# MainProc.net
KiCad netlist of a schematic drawn in Altium Designer
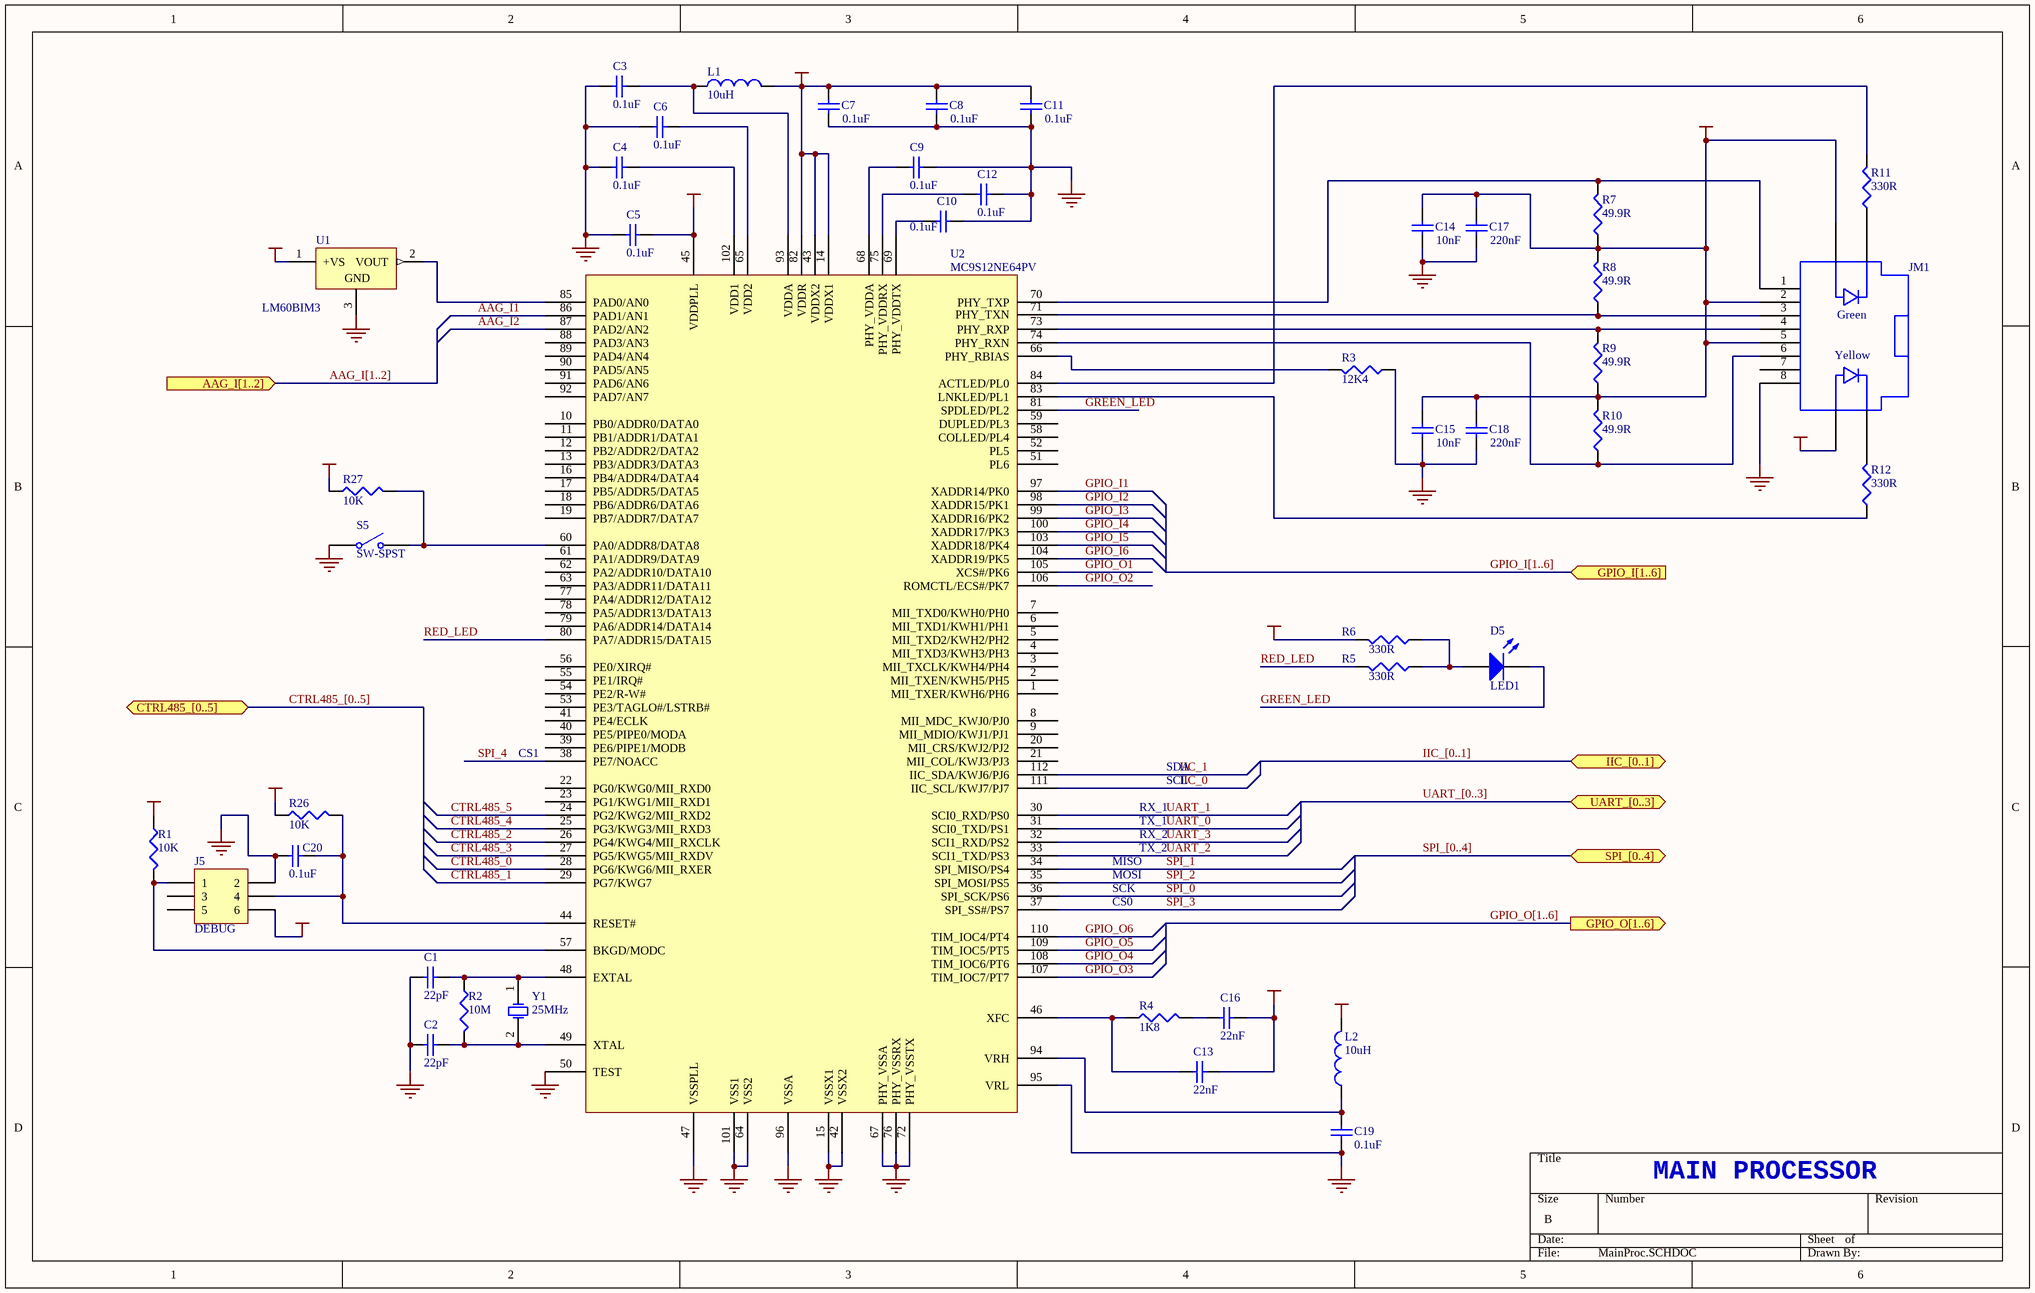
[diagram p0: MainProc.SCHDOC]

(export (version "E")
  (design (tool "Eeschema 10.0.6"))
  (components
    (comp (ref "C1")
      (value "22pF")
      (footprint "_1206")
      (description "Capacitor (Semiconductor SIM Model)")
      (fields (field (name "Comment") "Cap Semi") (field (name "PUBLISHER") "Altium Limited"))
      (libsource (lib "Miscellaneous Devices") (part "Cap Semi"))
    )
    (comp (ref "C2")
      (value "22pF")
      (footprint "_1206")
      (description "Capacitor (Semiconductor SIM Model)")
      (fields (field (name "Comment") "Cap Semi") (field (name "PUBLISHER") "Altium Limited"))
      (libsource (lib "Miscellaneous Devices") (part "Cap Semi"))
    )
    (comp (ref "C3")
      (value "0.1uF")
      (footprint "_0805")
      (description "Capacitor (Semiconductor SIM Model)")
      (fields (field (name "Comment") "Cap Semi") (field (name "PUBLISHER") "Altium Limited"))
      (libsource (lib "Miscellaneous Devices") (part "Cap Semi"))
    )
    (comp (ref "C4")
      (value "0.1uF")
      (footprint "_0805")
      (description "Capacitor (Semiconductor SIM Model)")
      (fields (field (name "Comment") "Cap Semi") (field (name "PUBLISHER") "Altium Limited"))
      (libsource (lib "Miscellaneous Devices") (part "Cap Semi"))
    )
    (comp (ref "C5")
      (value "0.1uF")
      (footprint "_0805")
      (description "Capacitor (Semiconductor SIM Model)")
      (fields (field (name "Comment") "Cap Semi") (field (name "PUBLISHER") "Altium Limited"))
      (libsource (lib "Miscellaneous Devices") (part "Cap Semi"))
    )
    (comp (ref "C6")
      (value "0.1uF")
      (footprint "_0805")
      (description "Capacitor (Semiconductor SIM Model)")
      (fields (field (name "Comment") "Cap Semi") (field (name "PUBLISHER") "Altium Limited"))
      (libsource (lib "Miscellaneous Devices") (part "Cap Semi"))
    )
    (comp (ref "C7")
      (value "0.1uF")
      (footprint "_0805")
      (description "Capacitor (Semiconductor SIM Model)")
      (fields (field (name "Comment") "Cap Semi") (field (name "PUBLISHER") "Altium Limited"))
      (libsource (lib "Miscellaneous Devices") (part "Cap Semi"))
    )
    (comp (ref "C8")
      (value "0.1uF")
      (footprint "_0805")
      (description "Capacitor (Semiconductor SIM Model)")
      (fields (field (name "Comment") "Cap Semi") (field (name "PUBLISHER") "Altium Limited"))
      (libsource (lib "Miscellaneous Devices") (part "Cap Semi"))
    )
    (comp (ref "C9")
      (value "0.1uF")
      (footprint "_0805")
      (description "Capacitor (Semiconductor SIM Model)")
      (fields (field (name "Comment") "Cap Semi") (field (name "PUBLISHER") "Altium Limited"))
      (libsource (lib "Miscellaneous Devices") (part "Cap Semi"))
    )
    (comp (ref "C10")
      (value "0.1uF")
      (footprint "_0805")
      (description "Capacitor (Semiconductor SIM Model)")
      (fields (field (name "Comment") "Cap Semi") (field (name "PUBLISHER") "Altium Limited"))
      (libsource (lib "Miscellaneous Devices") (part "Cap Semi"))
    )
    (comp (ref "C11")
      (value "0.1uF")
      (footprint "_0805")
      (description "Capacitor (Semiconductor SIM Model)")
      (fields (field (name "Comment") "Cap Semi") (field (name "PUBLISHER") "Altium Limited"))
      (libsource (lib "Miscellaneous Devices") (part "Cap Semi"))
    )
    (comp (ref "C12")
      (value "0.1uF")
      (footprint "_0805")
      (description "Capacitor (Semiconductor SIM Model)")
      (fields (field (name "Comment") "Cap Semi") (field (name "PUBLISHER") "Altium Limited"))
      (libsource (lib "Miscellaneous Devices") (part "Cap Semi"))
    )
    (comp (ref "C13")
      (value "22nF")
      (footprint "_0805")
      (description "Capacitor (Semiconductor SIM Model)")
      (fields (field (name "Comment") "Cap Semi") (field (name "PUBLISHER") "Altium Limited"))
      (libsource (lib "Miscellaneous Devices") (part "Cap Semi"))
    )
    (comp (ref "C14")
      (value "10nF")
      (footprint "_0805")
      (description "Capacitor (Semiconductor SIM Model)")
      (fields (field (name "Comment") "Cap Semi") (field (name "PUBLISHER") "Altium Limited"))
      (libsource (lib "Miscellaneous Devices") (part "Cap Semi"))
    )
    (comp (ref "C15")
      (value "10nF")
      (footprint "_0805")
      (description "Capacitor (Semiconductor SIM Model)")
      (fields (field (name "Comment") "Cap Semi") (field (name "PUBLISHER") "Altium Limited"))
      (libsource (lib "Miscellaneous Devices") (part "Cap Semi"))
    )
    (comp (ref "C16")
      (value "22nF")
      (footprint "_0805")
      (description "Capacitor (Semiconductor SIM Model)")
      (fields (field (name "Comment") "Cap Semi") (field (name "PUBLISHER") "Altium Limited"))
      (libsource (lib "Miscellaneous Devices") (part "Cap Semi"))
    )
    (comp (ref "C17")
      (value "220nF")
      (footprint "_0805")
      (description "Capacitor (Semiconductor SIM Model)")
      (fields (field (name "Comment") "Cap Semi") (field (name "PUBLISHER") "Altium Limited"))
      (libsource (lib "Miscellaneous Devices") (part "Cap Semi"))
    )
    (comp (ref "C18")
      (value "220nF")
      (footprint "_0805")
      (description "Capacitor (Semiconductor SIM Model)")
      (fields (field (name "Comment") "Cap Semi") (field (name "PUBLISHER") "Altium Limited"))
      (libsource (lib "Miscellaneous Devices") (part "Cap Semi"))
    )
    (comp (ref "C19")
      (value "0.1uF")
      (footprint "_0805")
      (description "Capacitor (Semiconductor SIM Model)")
      (fields (field (name "Comment") "Cap Semi") (field (name "PUBLISHER") "Altium Limited"))
      (libsource (lib "Miscellaneous Devices") (part "Cap Semi"))
    )
    (comp (ref "C20")
      (value "0.1uF")
      (footprint "_0805")
      (description "Capacitor (Semiconductor SIM Model)")
      (fields (field (name "Comment") "Cap Semi") (field (name "PUBLISHER") "Altium Limited"))
      (libsource (lib "Miscellaneous Devices") (part "Cap Semi"))
    )
    (comp (ref "D5")
      (value "LED1")
      (footprint "LED_PCB")
      (description "Typical RED GaAs LED")
      (fields (field (name "PUBLISHER") "Altium Limited"))
      (libsource (lib "Miscellaneous Devices") (part "LED1"))
    )
    (comp (ref "J5")
      (value "DEBUG")
      (footprint "HDR2X3")
      (description "Header, 3-Pin, Dual row")
      (fields (field (name "PUBLISHER") "Altium Limited"))
      (libsource (lib "Miscellaneous Connectors") (part "Header 3X2"))
    )
    (comp (ref "JM1")
      (value "JACK_RJ45_LED")
      (footprint "JACK_RJ45_LEDS")
      (description "RJ45 Connector Jack with Leds")
      (libsource (lib "Custom") (part "JACK_RJ45_LED"))
    )
    (comp (ref "L1")
      (value "10uH")
      (footprint "_0805")
      (description "Inductor")
      (fields (field (name "PUBLISHER") "Altium Limited"))
      (libsource (lib "Miscellaneous Devices") (part "Inductor"))
    )
    (comp (ref "L2")
      (value "10uH")
      (footprint "_0805")
      (description "Inductor")
      (fields (field (name "PUBLISHER") "Altium Limited"))
      (libsource (lib "Miscellaneous Devices") (part "Inductor"))
    )
    (comp (ref "R1")
      (value "10K")
      (footprint "_0805")
      (description "Resistor")
      (fields (field (name "Comment") "Res3") (field (name "PUBLISHER") "Altium Limited"))
      (libsource (lib "Miscellaneous Devices") (part "Res3"))
    )
    (comp (ref "R2")
      (value "10M")
      (footprint "_1206")
      (description "Resistor")
      (fields (field (name "Comment") "Res3") (field (name "PUBLISHER") "Altium Limited"))
      (libsource (lib "Miscellaneous Devices") (part "Res3"))
    )
    (comp (ref "R3")
      (value "12K4")
      (footprint "_0805")
      (description "Resistor")
      (fields (field (name "Comment") "Res3") (field (name "PUBLISHER") "Altium Limited"))
      (libsource (lib "Miscellaneous Devices") (part "Res3"))
    )
    (comp (ref "R4")
      (value "1K8")
      (footprint "_0805")
      (description "Resistor")
      (fields (field (name "Comment") "Res3") (field (name "PUBLISHER") "Altium Limited"))
      (libsource (lib "Miscellaneous Devices") (part "Res3"))
    )
    (comp (ref "R5")
      (value "330R")
      (footprint "_0805")
      (description "Resistor")
      (fields (field (name "Comment") "Res3") (field (name "PUBLISHER") "Altium Limited"))
      (libsource (lib "Miscellaneous Devices") (part "Res3"))
    )
    (comp (ref "R6")
      (value "330R")
      (footprint "_0805")
      (description "Resistor")
      (fields (field (name "Comment") "Res3") (field (name "PUBLISHER") "Altium Limited"))
      (libsource (lib "Miscellaneous Devices") (part "Res3"))
    )
    (comp (ref "R7")
      (value "49.9R")
      (footprint "_0805")
      (description "Resistor")
      (fields (field (name "Comment") "Res3") (field (name "PUBLISHER") "Altium Limited"))
      (libsource (lib "Miscellaneous Devices") (part "Res3"))
    )
    (comp (ref "R8")
      (value "49.9R")
      (footprint "_0805")
      (description "Resistor")
      (fields (field (name "Comment") "Res3") (field (name "PUBLISHER") "Altium Limited"))
      (libsource (lib "Miscellaneous Devices") (part "Res3"))
    )
    (comp (ref "R9")
      (value "49.9R")
      (footprint "_0805")
      (description "Resistor")
      (fields (field (name "Comment") "Res3") (field (name "PUBLISHER") "Altium Limited"))
      (libsource (lib "Miscellaneous Devices") (part "Res3"))
    )
    (comp (ref "R10")
      (value "49.9R")
      (footprint "_0805")
      (description "Resistor")
      (fields (field (name "Comment") "Res3") (field (name "PUBLISHER") "Altium Limited"))
      (libsource (lib "Miscellaneous Devices") (part "Res3"))
    )
    (comp (ref "R11")
      (value "330R")
      (footprint "_0805")
      (description "Resistor")
      (fields (field (name "Comment") "Res3") (field (name "PUBLISHER") "Altium Limited"))
      (libsource (lib "Miscellaneous Devices") (part "Res3"))
    )
    (comp (ref "R12")
      (value "330R")
      (footprint "_0805")
      (description "Resistor")
      (fields (field (name "Comment") "Res3") (field (name "PUBLISHER") "Altium Limited"))
      (libsource (lib "Miscellaneous Devices") (part "Res3"))
    )
    (comp (ref "R26")
      (value "10K")
      (footprint "_0805")
      (description "Resistor")
      (fields (field (name "Comment") "Res3") (field (name "PUBLISHER") "Altium Limited"))
      (libsource (lib "Miscellaneous Devices") (part "Res3"))
    )
    (comp (ref "R27")
      (value "10K")
      (footprint "_0805")
      (description "Resistor")
      (fields (field (name "Comment") "Res3") (field (name "PUBLISHER") "Altium Limited"))
      (libsource (lib "Miscellaneous Devices") (part "Res3"))
    )
    (comp (ref "S5")
      (value "SW-SPST")
      (footprint "SWITCH")
      (description "Single-Pole, Single-Throw Switch")
      (fields (field (name "PUBLISHER") "Altium Limited"))
      (libsource (lib "Miscellaneous Devices") (part "SW-SPST"))
    )
    (comp (ref "U1")
      (value "LM60BIM3")
      (footprint "MA03B")
      (description "2.7V, SOT-23 Temperature Sensor")
      (fields (field (name "PUBLISHER") "Altium Limited"))
      (libsource (lib "NSC Sensor Temperature Sensor") (part "LM60BIM3"))
    )
    (comp (ref "U2")
      (value "MC9S12NE64PV")
      (footprint "QFP20x20-G112/Y1.6N")
      (description "Integrated Ethernet Controller")
      (libsource (lib "Custom") (part "MC9S12NE64PV"))
    )
    (comp (ref "Y1")
      (value "25MHz")
      (footprint "HC49/4H_SMX")
      (description "Crystal Oscillator")
      (fields (field (name "Comment") "XTAL") (field (name "PUBLISHER") "Altium Limited"))
      (libsource (lib "Miscellaneous Devices") (part "XTAL"))
    )
  )
  (nets
    (net (code "1") (name "/AAG_I1") (class "Default")
      (node (ref "U2") (pin "86") (pinfunction "PAD1/AN1_86") (pintype "passive"))
    )
    (net (code "2") (name "/AAG_I2") (class "Default")
      (node (ref "U2") (pin "87") (pinfunction "PAD2/AN2_87") (pintype "passive"))
    )
    (net (code "4") (name "/CTRL485_0") (class "Default")
      (node (ref "U2") (pin "28") (pinfunction "PG6/KWG6/MII_RXER_28") (pintype "passive"))
    )
    (net (code "5") (name "/CTRL485_1") (class "Default")
      (node (ref "U2") (pin "29") (pinfunction "PG7/KWG7_29") (pintype "passive"))
    )
    (net (code "6") (name "/CTRL485_2") (class "Default")
      (node (ref "U2") (pin "26") (pinfunction "PG4/KWG4/MII_RXCLK_26") (pintype "passive"))
    )
    (net (code "7") (name "/CTRL485_3") (class "Default")
      (node (ref "U2") (pin "27") (pinfunction "PG5/KWG5/MII_RXDV_27") (pintype "passive"))
    )
    (net (code "8") (name "/CTRL485_4") (class "Default")
      (node (ref "U2") (pin "25") (pinfunction "PG3/KWG3/MII_RXD3_25") (pintype "passive"))
    )
    (net (code "9") (name "/CTRL485_5") (class "Default")
      (node (ref "U2") (pin "24") (pinfunction "PG2/KWG2/MII_RXD2_24") (pintype "passive"))
    )
    (net (code "11") (name "/GPIO_I1") (class "Default")
      (node (ref "U2") (pin "97") (pinfunction "XADDR14/PK0_97") (pintype "passive"))
    )
    (net (code "12") (name "/GPIO_I2") (class "Default")
      (node (ref "U2") (pin "98") (pinfunction "XADDR15/PK1_98") (pintype "passive"))
    )
    (net (code "13") (name "/GPIO_I3") (class "Default")
      (node (ref "U2") (pin "99") (pinfunction "XADDR16/PK2_99") (pintype "passive"))
    )
    (net (code "14") (name "/GPIO_I4") (class "Default")
      (node (ref "U2") (pin "100") (pinfunction "XADDR17/PK3_100") (pintype "passive"))
    )
    (net (code "15") (name "/GPIO_I5") (class "Default")
      (node (ref "U2") (pin "103") (pinfunction "XADDR18/PK4_103") (pintype "passive"))
    )
    (net (code "16") (name "/GPIO_I6") (class "Default")
      (node (ref "U2") (pin "104") (pinfunction "XADDR19/PK5_104") (pintype "passive"))
    )
    (net (code "18") (name "/GPIO_O1") (class "Default")
      (node (ref "U2") (pin "105") (pinfunction "XCS#/PK6_105") (pintype "passive"))
    )
    (net (code "19") (name "/GPIO_O2") (class "Default")
      (node (ref "U2") (pin "106") (pinfunction "ROMCTL/ECS#/PK7_106") (pintype "passive"))
    )
    (net (code "20") (name "/GPIO_O3") (class "Default")
      (node (ref "U2") (pin "107") (pinfunction "TIM_IOC7/PT7_107") (pintype "passive"))
    )
    (net (code "21") (name "/GPIO_O4") (class "Default")
      (node (ref "U2") (pin "108") (pinfunction "TIM_IOC6/PT6_108") (pintype "passive"))
    )
    (net (code "22") (name "/GPIO_O5") (class "Default")
      (node (ref "U2") (pin "109") (pinfunction "TIM_IOC5/PT5_109") (pintype "passive"))
    )
    (net (code "23") (name "/GPIO_O6") (class "Default")
      (node (ref "U2") (pin "110") (pinfunction "TIM_IOC4/PT4_110") (pintype "passive"))
    )
    (net (code "25") (name "/GREEN_LED") (class "Default")
      (node (ref "D5") (pin "2") (pinfunction "K_2") (pintype "passive"))
      (node (ref "U2") (pin "81") (pinfunction "SPDLED/PL2_81") (pintype "passive"))
    )
    (net (code "26") (name "/IIC_0") (class "Default")
      (node (ref "U2") (pin "111") (pinfunction "IIC_SCL/KWJ7/PJ7_111") (pintype "passive"))
    )
    (net (code "27") (name "/IIC_1") (class "Default")
      (node (ref "U2") (pin "112") (pinfunction "IIC_SDA/KWJ6/PJ6_112") (pintype "passive"))
    )
    (net (code "29") (name "/RED_LED") (class "Default")
      (node (ref "R5") (pin "2") (pinfunction "2_2") (pintype "passive"))
      (node (ref "U2") (pin "80") (pinfunction "PA7/ADDR15/DATA15_80") (pintype "passive"))
    )
    (net (code "30") (name "/SPI_0") (class "Default")
      (node (ref "U2") (pin "36") (pinfunction "SPI_SCK/PS6_36") (pintype "passive"))
    )
    (net (code "31") (name "/SPI_1") (class "Default")
      (node (ref "U2") (pin "34") (pinfunction "SPI_MISO/PS4_34") (pintype "passive"))
    )
    (net (code "32") (name "/SPI_2") (class "Default")
      (node (ref "U2") (pin "35") (pinfunction "SPI_MOSI/PS5_35") (pintype "passive"))
    )
    (net (code "33") (name "/SPI_3") (class "Default")
      (node (ref "U2") (pin "37") (pinfunction "SPI_SS#/PS7_37") (pintype "passive"))
    )
    (net (code "34") (name "/SPI_4") (class "Default")
      (node (ref "U2") (pin "38") (pinfunction "PE7/NOACC_38") (pintype "passive"))
    )
    (net (code "36") (name "/UART_0") (class "Default")
      (node (ref "U2") (pin "31") (pinfunction "SCI0_TXD/PS1_31") (pintype "passive"))
    )
    (net (code "37") (name "/UART_1") (class "Default")
      (node (ref "U2") (pin "30") (pinfunction "SCI0_RXD/PS0_30") (pintype "passive"))
    )
    (net (code "38") (name "/UART_2") (class "Default")
      (node (ref "U2") (pin "33") (pinfunction "SCI1_TXD/PS3_33") (pintype "passive"))
    )
    (net (code "39") (name "/UART_3") (class "Default")
      (node (ref "U2") (pin "32") (pinfunction "SCI1_RXD/PS2_32") (pintype "passive"))
    )
    (net (code "41") (name "GND") (class "Default")
      (node (ref "C1") (pin "2") (pinfunction "2_2") (pintype "passive"))
      (node (ref "C10") (pin "1") (pinfunction "1_1") (pintype "passive"))
      (node (ref "C11") (pin "1") (pinfunction "1_1") (pintype "passive"))
      (node (ref "C12") (pin "1") (pinfunction "1_1") (pintype "passive"))
      (node (ref "C14") (pin "1") (pinfunction "1_1") (pintype "passive"))
      (node (ref "C15") (pin "1") (pinfunction "1_1") (pintype "passive"))
      (node (ref "C17") (pin "1") (pinfunction "1_1") (pintype "passive"))
      (node (ref "C18") (pin "1") (pinfunction "1_1") (pintype "passive"))
      (node (ref "C19") (pin "1") (pinfunction "1_1") (pintype "passive"))
      (node (ref "C2") (pin "2") (pinfunction "2_2") (pintype "passive"))
      (node (ref "C20") (pin "1") (pinfunction "1_1") (pintype "passive"))
      (node (ref "C3") (pin "1") (pinfunction "1_1") (pintype "passive"))
      (node (ref "C4") (pin "2") (pinfunction "2_2") (pintype "passive"))
      (node (ref "C5") (pin "2") (pinfunction "2_2") (pintype "passive"))
      (node (ref "C6") (pin "2") (pinfunction "2_2") (pintype "passive"))
      (node (ref "C7") (pin "1") (pinfunction "1_1") (pintype "passive"))
      (node (ref "C8") (pin "1") (pinfunction "1_1") (pintype "passive"))
      (node (ref "C9") (pin "1") (pinfunction "1_1") (pintype "passive"))
      (node (ref "J5") (pin "2") (pinfunction "2_2") (pintype "passive"))
      (node (ref "JM1") (pin "8") (pinfunction "8_8") (pintype "passive"))
      (node (ref "R3") (pin "1") (pinfunction "1_1") (pintype "passive"))
      (node (ref "S5") (pin "1") (pinfunction "COMMON_1") (pintype "passive"))
      (node (ref "U1") (pin "3") (pinfunction "GND_3") (pintype "power_in"))
      (node (ref "U2") (pin "101") (pinfunction "VSS1_101") (pintype "power_in"))
      (node (ref "U2") (pin "15") (pinfunction "VSSX1_15") (pintype "power_in"))
      (node (ref "U2") (pin "42") (pinfunction "VSSX2_42") (pintype "power_in"))
      (node (ref "U2") (pin "47") (pinfunction "VSSPLL_47") (pintype "power_in"))
      (node (ref "U2") (pin "50") (pinfunction "TEST_50") (pintype "passive"))
      (node (ref "U2") (pin "64") (pinfunction "VSS2_64") (pintype "power_in"))
      (node (ref "U2") (pin "67") (pinfunction "PHY_VSSA_67") (pintype "power_in"))
      (node (ref "U2") (pin "72") (pinfunction "PHY_VSSTX_72") (pintype "power_in"))
      (node (ref "U2") (pin "76") (pinfunction "PHY_VSSRX_76") (pintype "power_in"))
      (node (ref "U2") (pin "95") (pinfunction "VRL_95") (pintype "passive"))
      (node (ref "U2") (pin "96") (pinfunction "VSSA_96") (pintype "power_in"))
    )
    (net (code "42") (name "Net-(C16-Pad2)") (class "Default")
      (node (ref "C16") (pin "2") (pinfunction "2_2") (pintype "passive"))
      (node (ref "R4") (pin "2") (pinfunction "2_2") (pintype "passive"))
    )
    (net (code "43") (name "Net-(D5-A)") (class "Default")
      (node (ref "D5") (pin "1") (pinfunction "A_1") (pintype "passive"))
      (node (ref "R5") (pin "1") (pinfunction "1_1") (pintype "passive"))
      (node (ref "R6") (pin "1") (pinfunction "1_1") (pintype "passive"))
    )
    (net (code "44") (name "Net-(JM1-PadGK)") (class "Default")
      (node (ref "JM1") (pin "GK") (pinfunction "GK_GK") (pintype "passive"))
      (node (ref "R11") (pin "1") (pinfunction "1_1") (pintype "passive"))
    )
    (net (code "45") (name "Net-(JM1-PadYK)") (class "Default")
      (node (ref "JM1") (pin "YK") (pinfunction "YK_YK") (pintype "passive"))
      (node (ref "R12") (pin "2") (pinfunction "2_2") (pintype "passive"))
    )
    (net (code "46") (name "Net-(S5-NO)") (class "Default")
      (node (ref "R27") (pin "2") (pinfunction "2_2") (pintype "passive"))
      (node (ref "S5") (pin "2") (pinfunction "NO_2") (pintype "passive"))
      (node (ref "U2") (pin "60") (pinfunction "PA0/ADDR8/DATA8_60") (pintype "passive"))
    )
    (net (code "47") (name "Net-(U1-VOUT)") (class "Default")
      (node (ref "U1") (pin "2") (pinfunction "VOUT_2") (pintype "output"))
      (node (ref "U2") (pin "85") (pinfunction "PAD0/AN0_85") (pintype "passive"))
    )
    (net (code "48") (name "Net-(U2-ACTLED{slash}PL0)") (class "Default")
      (node (ref "R11") (pin "2") (pinfunction "2_2") (pintype "passive"))
      (node (ref "U2") (pin "84") (pinfunction "ACTLED/PL0_84") (pintype "passive"))
    )
    (net (code "49") (name "Net-(U2-BKGD{slash}MODC)") (class "Default")
      (node (ref "J5") (pin "1") (pinfunction "1_1") (pintype "passive"))
      (node (ref "R1") (pin "2") (pinfunction "2_2") (pintype "passive"))
      (node (ref "U2") (pin "57") (pinfunction "BKGD/MODC_57") (pintype "passive"))
    )
    (net (code "50") (name "Net-(U2-EXTAL)") (class "Default")
      (node (ref "C1") (pin "1") (pinfunction "1_1") (pintype "passive"))
      (node (ref "R2") (pin "1") (pinfunction "1_1") (pintype "passive"))
      (node (ref "U2") (pin "48") (pinfunction "EXTAL_48") (pintype "passive"))
      (node (ref "Y1") (pin "1") (pinfunction "OSC1_1") (pintype "passive"))
    )
    (net (code "51") (name "Net-(U2-LNKLED{slash}PL1)") (class "Default")
      (node (ref "R12") (pin "1") (pinfunction "1_1") (pintype "passive"))
      (node (ref "U2") (pin "83") (pinfunction "LNKLED/PL1_83") (pintype "passive"))
    )
    (net (code "52") (name "Net-(U2-PHY_RBIAS)") (class "Default")
      (node (ref "R3") (pin "2") (pinfunction "2_2") (pintype "passive"))
      (node (ref "U2") (pin "66") (pinfunction "PHY_RBIAS_66") (pintype "passive"))
    )
    (net (code "53") (name "Net-(U2-PHY_RXN)") (class "Default")
      (node (ref "JM1") (pin "6") (pinfunction "6_6") (pintype "passive"))
      (node (ref "R10") (pin "1") (pinfunction "1_1") (pintype "passive"))
      (node (ref "U2") (pin "74") (pinfunction "PHY_RXN_74") (pintype "passive"))
    )
    (net (code "54") (name "Net-(U2-PHY_RXP)") (class "Default")
      (node (ref "JM1") (pin "4") (pinfunction "4_4") (pintype "passive"))
      (node (ref "R9") (pin "2") (pinfunction "2_2") (pintype "passive"))
      (node (ref "U2") (pin "73") (pinfunction "PHY_RXP_73") (pintype "passive"))
    )
    (net (code "55") (name "Net-(U2-PHY_TXN)") (class "Default")
      (node (ref "JM1") (pin "3") (pinfunction "3_3") (pintype "passive"))
      (node (ref "R8") (pin "1") (pinfunction "1_1") (pintype "passive"))
      (node (ref "U2") (pin "71") (pinfunction "PHY_TXN_71") (pintype "passive"))
    )
    (net (code "56") (name "Net-(U2-PHY_TXP)") (class "Default")
      (node (ref "JM1") (pin "1") (pinfunction "1_1") (pintype "passive"))
      (node (ref "R7") (pin "2") (pinfunction "2_2") (pintype "passive"))
      (node (ref "U2") (pin "70") (pinfunction "PHY_TXP_70") (pintype "passive"))
    )
    (net (code "57") (name "Net-(U2-PHY_VDDA)") (class "Default")
      (node (ref "C9") (pin "2") (pinfunction "2_2") (pintype "passive"))
      (node (ref "U2") (pin "68") (pinfunction "PHY_VDDA_68") (pintype "power_in"))
    )
    (net (code "58") (name "Net-(U2-PHY_VDDRX)") (class "Default")
      (node (ref "C12") (pin "2") (pinfunction "2_2") (pintype "passive"))
      (node (ref "U2") (pin "75") (pinfunction "PHY_VDDRX_75") (pintype "power_in"))
    )
    (net (code "59") (name "Net-(U2-PHY_VDDTX)") (class "Default")
      (node (ref "C10") (pin "2") (pinfunction "2_2") (pintype "passive"))
      (node (ref "U2") (pin "69") (pinfunction "PHY_VDDTX_69") (pintype "power_in"))
    )
    (net (code "60") (name "Net-(U2-RESET#)") (class "Default")
      (node (ref "C20") (pin "2") (pinfunction "2_2") (pintype "passive"))
      (node (ref "J5") (pin "4") (pinfunction "4_4") (pintype "passive"))
      (node (ref "R26") (pin "2") (pinfunction "2_2") (pintype "passive"))
      (node (ref "U2") (pin "44") (pinfunction "RESET#_44") (pintype "passive"))
    )
    (net (code "61") (name "Net-(U2-VDD1)") (class "Default")
      (node (ref "C4") (pin "1") (pinfunction "1_1") (pintype "passive"))
      (node (ref "U2") (pin "102") (pinfunction "VDD1_102") (pintype "power_in"))
    )
    (net (code "62") (name "Net-(U2-VDD2)") (class "Default")
      (node (ref "C6") (pin "1") (pinfunction "1_1") (pintype "passive"))
      (node (ref "U2") (pin "65") (pinfunction "VDD2_65") (pintype "power_in"))
    )
    (net (code "63") (name "Net-(U2-VDDA)") (class "Default")
      (node (ref "C3") (pin "2") (pinfunction "2_2") (pintype "passive"))
      (node (ref "L1") (pin "1") (pinfunction "1_1") (pintype "passive"))
      (node (ref "U2") (pin "93") (pinfunction "VDDA_93") (pintype "power_in"))
    )
    (net (code "64") (name "Net-(U2-VRH)") (class "Default")
      (node (ref "C19") (pin "2") (pinfunction "2_2") (pintype "passive"))
      (node (ref "L2") (pin "1") (pinfunction "1_1") (pintype "passive"))
      (node (ref "U2") (pin "94") (pinfunction "VRH_94") (pintype "passive"))
    )
    (net (code "65") (name "Net-(U2-XFC)") (class "Default")
      (node (ref "C13") (pin "2") (pinfunction "2_2") (pintype "passive"))
      (node (ref "R4") (pin "1") (pinfunction "1_1") (pintype "passive"))
      (node (ref "U2") (pin "46") (pinfunction "XFC_46") (pintype "passive"))
    )
    (net (code "66") (name "Net-(U2-XTAL)") (class "Default")
      (node (ref "C2") (pin "1") (pinfunction "1_1") (pintype "passive"))
      (node (ref "R2") (pin "2") (pinfunction "2_2") (pintype "passive"))
      (node (ref "U2") (pin "49") (pinfunction "XTAL_49") (pintype "passive"))
      (node (ref "Y1") (pin "2") (pinfunction "OSC2_2") (pintype "passive"))
    )
    (net (code "67") (name "VCC_3V") (class "Default")
      (node (ref "C11") (pin "2") (pinfunction "2_2") (pintype "passive"))
      (node (ref "C14") (pin "2") (pinfunction "2_2") (pintype "passive"))
      (node (ref "C15") (pin "2") (pinfunction "2_2") (pintype "passive"))
      (node (ref "C17") (pin "2") (pinfunction "2_2") (pintype "passive"))
      (node (ref "C18") (pin "2") (pinfunction "2_2") (pintype "passive"))
      (node (ref "C7") (pin "2") (pinfunction "2_2") (pintype "passive"))
      (node (ref "C8") (pin "2") (pinfunction "2_2") (pintype "passive"))
      (node (ref "J5") (pin "6") (pinfunction "6_6") (pintype "passive"))
      (node (ref "JM1") (pin "2") (pinfunction "2_2") (pintype "passive"))
      (node (ref "JM1") (pin "5") (pinfunction "5_5") (pintype "passive"))
      (node (ref "JM1") (pin "GA") (pinfunction "GA_GA") (pintype "passive"))
      (node (ref "JM1") (pin "YA") (pinfunction "YA_YA") (pintype "passive"))
      (node (ref "L1") (pin "2") (pinfunction "2_2") (pintype "passive"))
      (node (ref "L2") (pin "2") (pinfunction "2_2") (pintype "passive"))
      (node (ref "R1") (pin "1") (pinfunction "1_1") (pintype "passive"))
      (node (ref "R10") (pin "2") (pinfunction "2_2") (pintype "passive"))
      (node (ref "R26") (pin "1") (pinfunction "1_1") (pintype "passive"))
      (node (ref "R27") (pin "1") (pinfunction "1_1") (pintype "passive"))
      (node (ref "R6") (pin "2") (pinfunction "2_2") (pintype "passive"))
      (node (ref "R7") (pin "1") (pinfunction "1_1") (pintype "passive"))
      (node (ref "R8") (pin "2") (pinfunction "2_2") (pintype "passive"))
      (node (ref "R9") (pin "1") (pinfunction "1_1") (pintype "passive"))
      (node (ref "U1") (pin "1") (pinfunction "+VS_1") (pintype "power_in"))
      (node (ref "U2") (pin "14") (pinfunction "VDDX1_14") (pintype "power_in"))
      (node (ref "U2") (pin "43") (pinfunction "VDDX2_43") (pintype "power_in"))
      (node (ref "U2") (pin "82") (pinfunction "VDDR_82") (pintype "power_in"))
    )
    (net (code "68") (name "VDD_PLL") (class "Default")
      (node (ref "C13") (pin "1") (pinfunction "1_1") (pintype "passive"))
      (node (ref "C16") (pin "1") (pinfunction "1_1") (pintype "passive"))
      (node (ref "C5") (pin "1") (pinfunction "1_1") (pintype "passive"))
      (node (ref "U2") (pin "45") (pinfunction "VDDPLL_45") (pintype "power_in"))
    )
    (net (code "69") (name "unconnected-(J5-Pad3)") (class "Default")
      (node (ref "J5") (pin "3") (pinfunction "3_3") (pintype "passive"))
    )
    (net (code "70") (name "unconnected-(J5-Pad5)") (class "Default")
      (node (ref "J5") (pin "5") (pinfunction "5_5") (pintype "passive"))
    )
    (net (code "71") (name "unconnected-(JM1-Pad7)") (class "Default")
      (node (ref "JM1") (pin "7") (pinfunction "7_7") (pintype "passive"))
    )
    (net (code "72") (name "unconnected-(U2-COLLED{slash}PL4-Pad58)") (class "Default")
      (node (ref "U2") (pin "58") (pinfunction "COLLED/PL4_58") (pintype "passive"))
    )
    (net (code "73") (name "unconnected-(U2-DUPLED{slash}PL3-Pad59)") (class "Default")
      (node (ref "U2") (pin "59") (pinfunction "DUPLED/PL3_59") (pintype "passive"))
    )
    (net (code "74") (name "unconnected-(U2-MII_COL{slash}KWJ3{slash}PJ3-Pad21)") (class "Default")
      (node (ref "U2") (pin "21") (pinfunction "MII_COL/KWJ3/PJ3_21") (pintype "passive"))
    )
    (net (code "75") (name "unconnected-(U2-MII_CRS{slash}KWJ2{slash}PJ2-Pad20)") (class "Default")
      (node (ref "U2") (pin "20") (pinfunction "MII_CRS/KWJ2/PJ2_20") (pintype "passive"))
    )
    (net (code "76") (name "unconnected-(U2-MII_MDC_KWJ0{slash}PJ0-Pad8)") (class "Default")
      (node (ref "U2") (pin "8") (pinfunction "MII_MDC_KWJ0/PJ0_8") (pintype "passive"))
    )
    (net (code "77") (name "unconnected-(U2-MII_MDIO{slash}KWJ1{slash}PJ1-Pad9)") (class "Default")
      (node (ref "U2") (pin "9") (pinfunction "MII_MDIO/KWJ1/PJ1_9") (pintype "passive"))
    )
    (net (code "78") (name "unconnected-(U2-MII_TXCLK{slash}KWH4{slash}PH4-Pad3)") (class "Default")
      (node (ref "U2") (pin "3") (pinfunction "MII_TXCLK/KWH4/PH4_3") (pintype "passive"))
    )
    (net (code "79") (name "unconnected-(U2-MII_TXD0{slash}KWH0{slash}PH0-Pad7)") (class "Default")
      (node (ref "U2") (pin "7") (pinfunction "MII_TXD0/KWH0/PH0_7") (pintype "passive"))
    )
    (net (code "80") (name "unconnected-(U2-MII_TXD1{slash}KWH1{slash}PH1-Pad6)") (class "Default")
      (node (ref "U2") (pin "6") (pinfunction "MII_TXD1/KWH1/PH1_6") (pintype "passive"))
    )
    (net (code "81") (name "unconnected-(U2-MII_TXD2{slash}KWH2{slash}PH2-Pad5)") (class "Default")
      (node (ref "U2") (pin "5") (pinfunction "MII_TXD2/KWH2/PH2_5") (pintype "passive"))
    )
    (net (code "82") (name "unconnected-(U2-MII_TXD3{slash}KWH3{slash}PH3-Pad4)") (class "Default")
      (node (ref "U2") (pin "4") (pinfunction "MII_TXD3/KWH3/PH3_4") (pintype "passive"))
    )
    (net (code "83") (name "unconnected-(U2-MII_TXEN{slash}KWH5{slash}PH5-Pad2)") (class "Default")
      (node (ref "U2") (pin "2") (pinfunction "MII_TXEN/KWH5/PH5_2") (pintype "passive"))
    )
    (net (code "84") (name "unconnected-(U2-MII_TXER{slash}KWH6{slash}PH6-Pad1)") (class "Default")
      (node (ref "U2") (pin "1") (pinfunction "MII_TXER/KWH6/PH6_1") (pintype "passive"))
    )
    (net (code "85") (name "unconnected-(U2-PA1{slash}ADDR9{slash}DATA9-Pad61)") (class "Default")
      (node (ref "U2") (pin "61") (pinfunction "PA1/ADDR9/DATA9_61") (pintype "passive"))
    )
    (net (code "86") (name "unconnected-(U2-PA2{slash}ADDR10{slash}DATA10-Pad62)") (class "Default")
      (node (ref "U2") (pin "62") (pinfunction "PA2/ADDR10/DATA10_62") (pintype "passive"))
    )
    (net (code "87") (name "unconnected-(U2-PA3{slash}ADDR11{slash}DATA11-Pad63)") (class "Default")
      (node (ref "U2") (pin "63") (pinfunction "PA3/ADDR11/DATA11_63") (pintype "passive"))
    )
    (net (code "88") (name "unconnected-(U2-PA4{slash}ADDR12{slash}DATA12-Pad77)") (class "Default")
      (node (ref "U2") (pin "77") (pinfunction "PA4/ADDR12/DATA12_77") (pintype "passive"))
    )
    (net (code "89") (name "unconnected-(U2-PA5{slash}ADDR13{slash}DATA13-Pad78)") (class "Default")
      (node (ref "U2") (pin "78") (pinfunction "PA5/ADDR13/DATA13_78") (pintype "passive"))
    )
    (net (code "90") (name "unconnected-(U2-PA6{slash}ADDR14{slash}DATA14-Pad79)") (class "Default")
      (node (ref "U2") (pin "79") (pinfunction "PA6/ADDR14/DATA14_79") (pintype "passive"))
    )
    (net (code "91") (name "unconnected-(U2-PAD3{slash}AN3-Pad88)") (class "Default")
      (node (ref "U2") (pin "88") (pinfunction "PAD3/AN3_88") (pintype "passive"))
    )
    (net (code "92") (name "unconnected-(U2-PAD4{slash}AN4-Pad89)") (class "Default")
      (node (ref "U2") (pin "89") (pinfunction "PAD4/AN4_89") (pintype "passive"))
    )
    (net (code "93") (name "unconnected-(U2-PAD5{slash}AN5-Pad90)") (class "Default")
      (node (ref "U2") (pin "90") (pinfunction "PAD5/AN5_90") (pintype "passive"))
    )
    (net (code "94") (name "unconnected-(U2-PAD6{slash}AN6-Pad91)") (class "Default")
      (node (ref "U2") (pin "91") (pinfunction "PAD6/AN6_91") (pintype "passive"))
    )
    (net (code "95") (name "unconnected-(U2-PAD7{slash}AN7-Pad92)") (class "Default")
      (node (ref "U2") (pin "92") (pinfunction "PAD7/AN7_92") (pintype "passive"))
    )
    (net (code "96") (name "unconnected-(U2-PB0{slash}ADDR0{slash}DATA0-Pad10)") (class "Default")
      (node (ref "U2") (pin "10") (pinfunction "PB0/ADDR0/DATA0_10") (pintype "passive"))
    )
    (net (code "97") (name "unconnected-(U2-PB1{slash}ADDR1{slash}DATA1-Pad11)") (class "Default")
      (node (ref "U2") (pin "11") (pinfunction "PB1/ADDR1/DATA1_11") (pintype "passive"))
    )
    (net (code "98") (name "unconnected-(U2-PB2{slash}ADDR2{slash}DATA2-Pad12)") (class "Default")
      (node (ref "U2") (pin "12") (pinfunction "PB2/ADDR2/DATA2_12") (pintype "passive"))
    )
    (net (code "99") (name "unconnected-(U2-PB3{slash}ADDR3{slash}DATA3-Pad13)") (class "Default")
      (node (ref "U2") (pin "13") (pinfunction "PB3/ADDR3/DATA3_13") (pintype "passive"))
    )
    (net (code "100") (name "unconnected-(U2-PB4{slash}ADDR4{slash}DATA4-Pad16)") (class "Default")
      (node (ref "U2") (pin "16") (pinfunction "PB4/ADDR4/DATA4_16") (pintype "passive"))
    )
    (net (code "101") (name "unconnected-(U2-PB5{slash}ADDR5{slash}DATA5-Pad17)") (class "Default")
      (node (ref "U2") (pin "17") (pinfunction "PB5/ADDR5/DATA5_17") (pintype "passive"))
    )
    (net (code "102") (name "unconnected-(U2-PB6{slash}ADDR6{slash}DATA6-Pad18)") (class "Default")
      (node (ref "U2") (pin "18") (pinfunction "PB6/ADDR6/DATA6_18") (pintype "passive"))
    )
    (net (code "103") (name "unconnected-(U2-PB7{slash}ADDR7{slash}DATA7-Pad19)") (class "Default")
      (node (ref "U2") (pin "19") (pinfunction "PB7/ADDR7/DATA7_19") (pintype "passive"))
    )
    (net (code "104") (name "unconnected-(U2-PE0{slash}XIRQ#-Pad56)") (class "Default")
      (node (ref "U2") (pin "56") (pinfunction "PE0/XIRQ#_56") (pintype "passive"))
    )
    (net (code "105") (name "unconnected-(U2-PE1{slash}IRQ#-Pad55)") (class "Default")
      (node (ref "U2") (pin "55") (pinfunction "PE1/IRQ#_55") (pintype "passive"))
    )
    (net (code "106") (name "unconnected-(U2-PE2{slash}R-W#-Pad54)") (class "Default")
      (node (ref "U2") (pin "54") (pinfunction "PE2/R-W#_54") (pintype "passive"))
    )
    (net (code "107") (name "unconnected-(U2-PE3{slash}TAGLO#{slash}LSTRB#-Pad53)") (class "Default")
      (node (ref "U2") (pin "53") (pinfunction "PE3/TAGLO#/LSTRB#_53") (pintype "passive"))
    )
    (net (code "108") (name "unconnected-(U2-PE4{slash}ECLK-Pad41)") (class "Default")
      (node (ref "U2") (pin "41") (pinfunction "PE4/ECLK_41") (pintype "passive"))
    )
    (net (code "109") (name "unconnected-(U2-PE5{slash}PIPE0{slash}MODA-Pad40)") (class "Default")
      (node (ref "U2") (pin "40") (pinfunction "PE5/PIPE0/MODA_40") (pintype "passive"))
    )
    (net (code "110") (name "unconnected-(U2-PE6{slash}PIPE1{slash}MODB-Pad39)") (class "Default")
      (node (ref "U2") (pin "39") (pinfunction "PE6/PIPE1/MODB_39") (pintype "passive"))
    )
    (net (code "111") (name "unconnected-(U2-PG0{slash}KWG0{slash}MII_RXD0-Pad22)") (class "Default")
      (node (ref "U2") (pin "22") (pinfunction "PG0/KWG0/MII_RXD0_22") (pintype "passive"))
    )
    (net (code "112") (name "unconnected-(U2-PG1{slash}KWG1{slash}MII_RXD1-Pad23)") (class "Default")
      (node (ref "U2") (pin "23") (pinfunction "PG1/KWG1/MII_RXD1_23") (pintype "passive"))
    )
    (net (code "113") (name "unconnected-(U2-PL5-Pad52)") (class "Default")
      (node (ref "U2") (pin "52") (pinfunction "PL5_52") (pintype "passive"))
    )
    (net (code "114") (name "unconnected-(U2-PL6-Pad51)") (class "Default")
      (node (ref "U2") (pin "51") (pinfunction "PL6_51") (pintype "passive"))
    )
  )
)
